# usbxlater.net
KiCad netlist of a schematic drawn in EAGLE
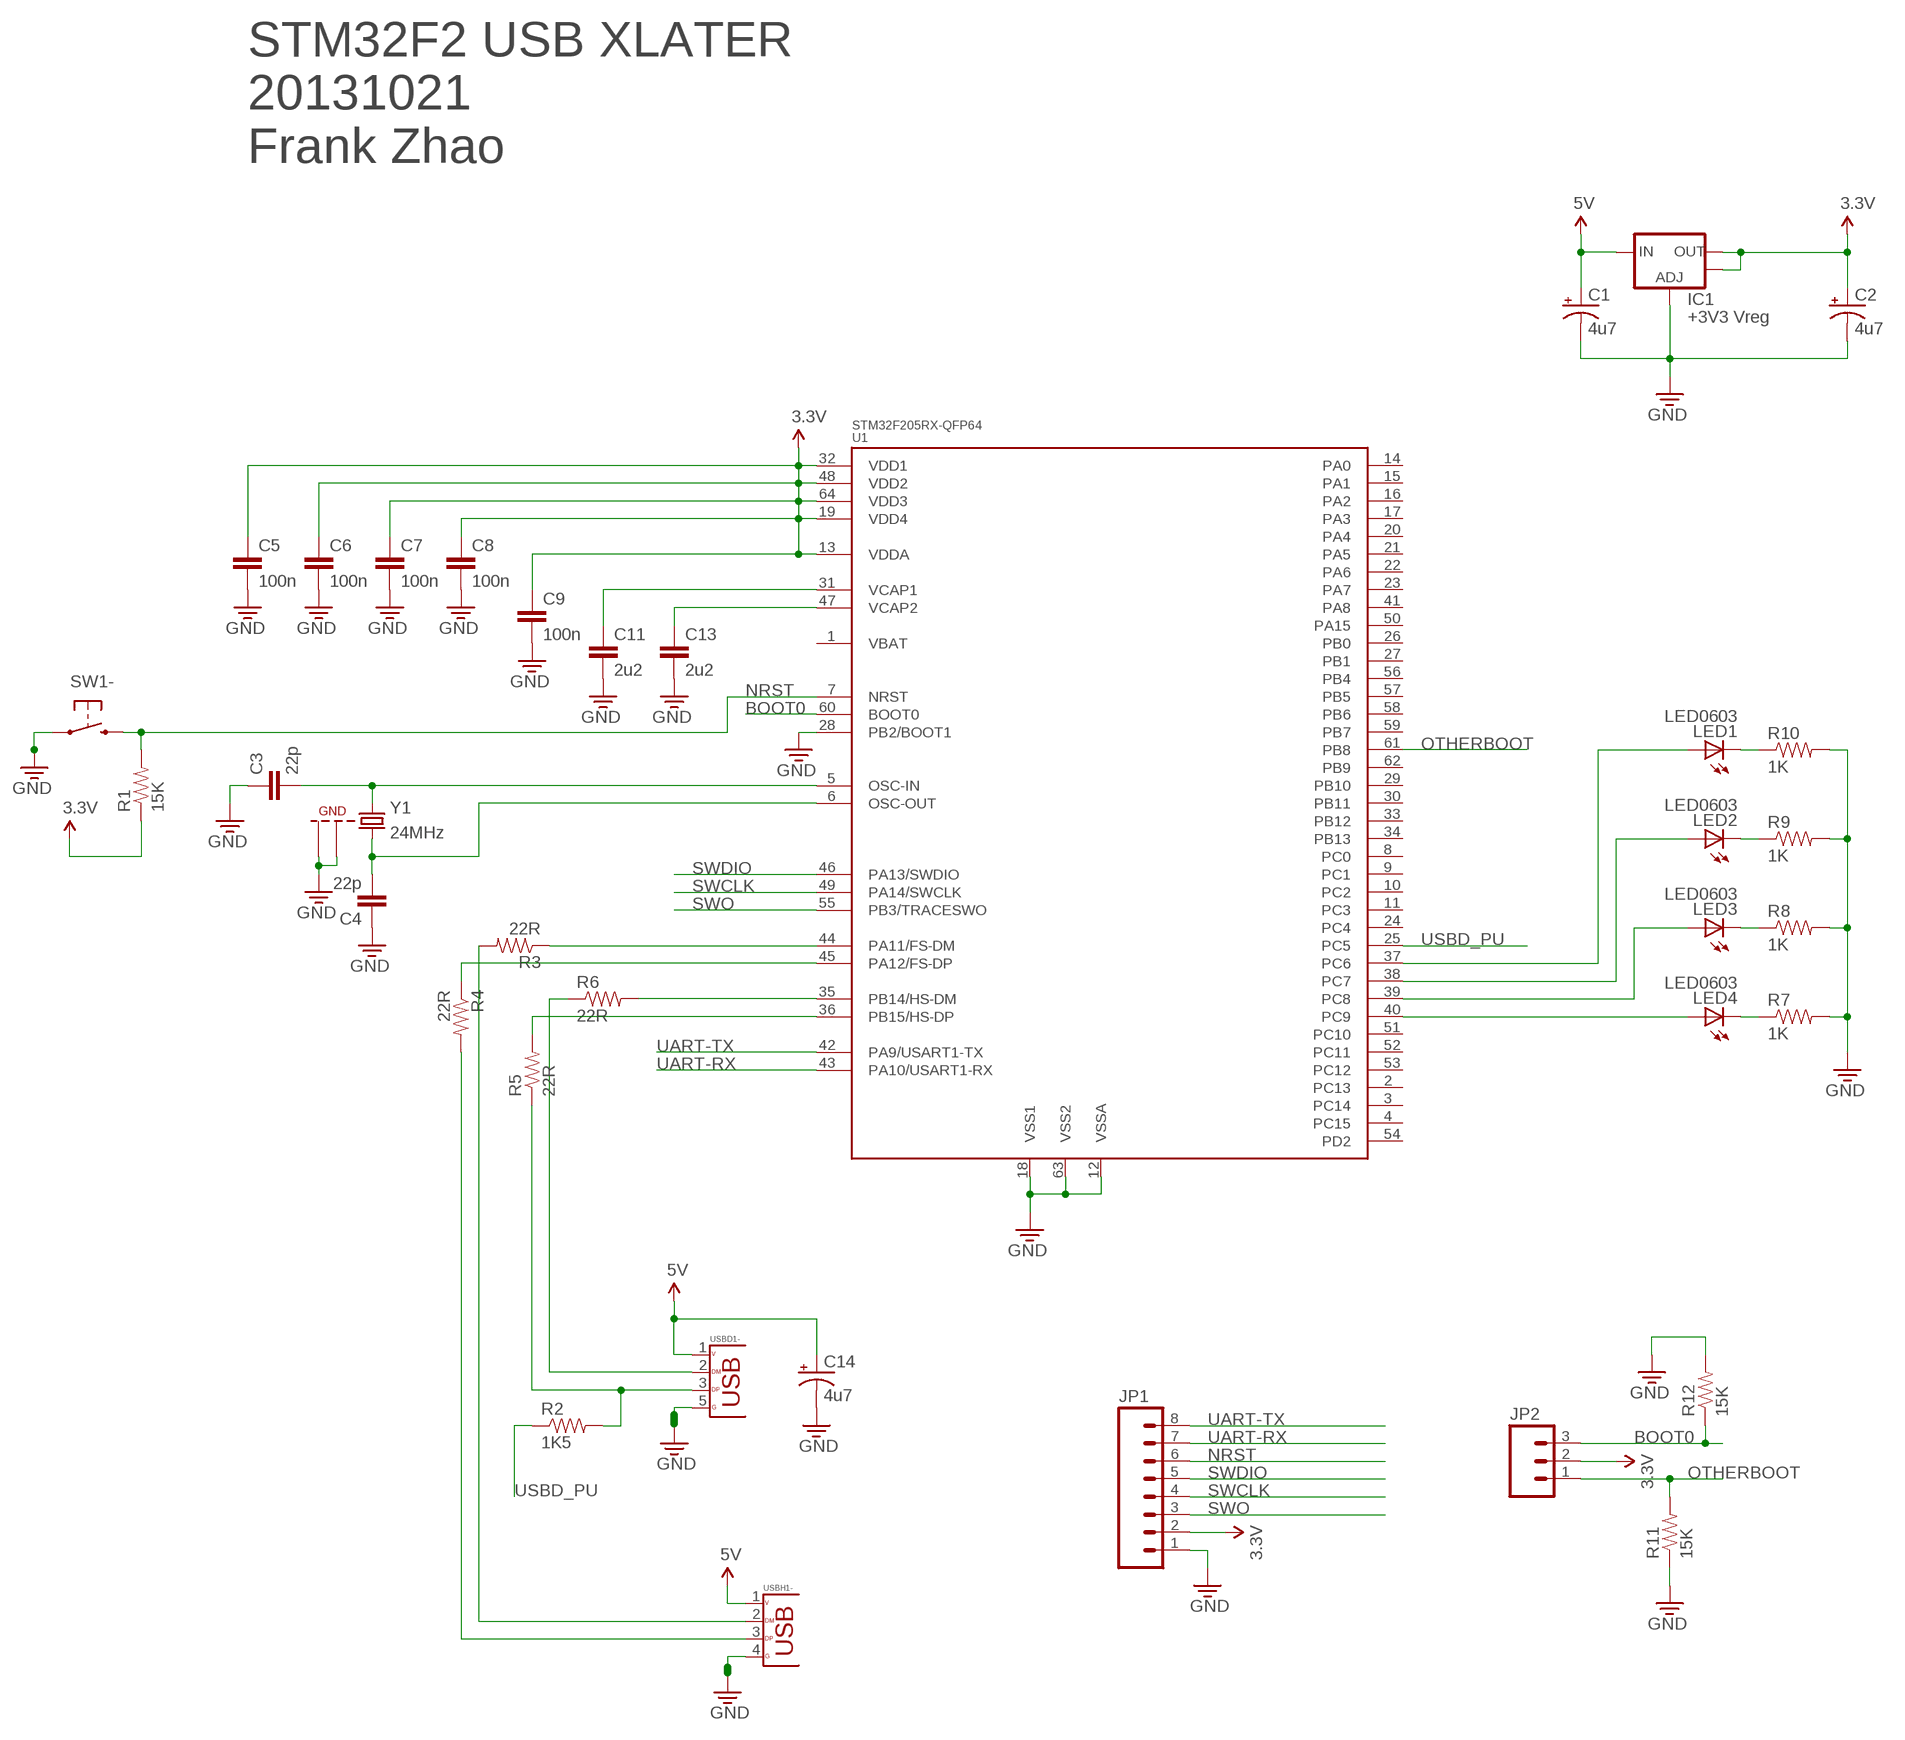
[diagram p0: schematic, sheet 1]

(export (version "E")
  (design (tool "Eeschema 10.0.6"))
  (components
    (comp (ref "C1")
      (value "4u7")
      (footprint "eagle-import:EIA3216")
      (libsource (lib "eagle-import") (part "CAP_POL1206"))
    )
    (comp (ref "C2")
      (value "4u7")
      (footprint "eagle-import:EIA3216")
      (libsource (lib "eagle-import") (part "CAP_POL1206"))
    )
    (comp (ref "C3")
      (value "22p")
      (footprint "eagle-import:0603-CAP-NOLEAK")
      (libsource (lib "eagle-import") (part "CAP0603-CAP-NOLEAK"))
    )
    (comp (ref "C4")
      (value "22p")
      (footprint "eagle-import:0603-CAP-NOLEAK")
      (libsource (lib "eagle-import") (part "CAP0603-CAP-NOLEAK"))
    )
    (comp (ref "C5")
      (value "100n")
      (footprint "eagle-import:0603-CAP-NOLEAK")
      (libsource (lib "eagle-import") (part "CAP0603-CAP-NOLEAK"))
    )
    (comp (ref "C6")
      (value "100n")
      (footprint "eagle-import:0603-CAP-NOLEAK")
      (libsource (lib "eagle-import") (part "CAP0603-CAP-NOLEAK"))
    )
    (comp (ref "C7")
      (value "100n")
      (footprint "eagle-import:0603-CAP-NOLEAK")
      (libsource (lib "eagle-import") (part "CAP0603-CAP-NOLEAK"))
    )
    (comp (ref "C8")
      (value "100n")
      (footprint "eagle-import:0603-CAP-NOLEAK")
      (libsource (lib "eagle-import") (part "CAP0603-CAP-NOLEAK"))
    )
    (comp (ref "C9")
      (value "100n")
      (footprint "eagle-import:0603-CAP-NOLEAK")
      (libsource (lib "eagle-import") (part "CAP0603-CAP-NOLEAK"))
    )
    (comp (ref "C11")
      (value "2u2")
      (footprint "eagle-import:0603-CAP-NOLEAK")
      (libsource (lib "eagle-import") (part "CAP0603-CAP-NOLEAK"))
    )
    (comp (ref "C13")
      (value "2u2")
      (footprint "eagle-import:0603-CAP-NOLEAK")
      (libsource (lib "eagle-import") (part "CAP0603-CAP-NOLEAK"))
    )
    (comp (ref "C14")
      (value "4u7")
      (footprint "eagle-import:EIA3216")
      (libsource (lib "eagle-import") (part "CAP_POL1206"))
    )
    (comp (ref "IC1")
      (value "+3V3 Vreg")
      (footprint "eagle-import:SOT223")
      (libsource (lib "eagle-import") (part "V_REG_LM1117SOT223"))
    )
    (comp (ref "JP1")
      (value "M081X08")
      (footprint "eagle-import:1X08")
      (libsource (lib "eagle-import") (part "M081X08"))
    )
    (comp (ref "JP2")
      (value "M03PTH")
      (footprint "eagle-import:1X03")
      (libsource (lib "eagle-import") (part "M03PTH"))
    )
    (comp (ref "LED1")
      (value "LED0603")
      (footprint "eagle-import:LED-0603")
      (libsource (lib "eagle-import") (part "LED0603"))
    )
    (comp (ref "LED2")
      (value "LED0603")
      (footprint "eagle-import:LED-0603")
      (libsource (lib "eagle-import") (part "LED0603"))
    )
    (comp (ref "LED3")
      (value "LED0603")
      (footprint "eagle-import:LED-0603")
      (libsource (lib "eagle-import") (part "LED0603"))
    )
    (comp (ref "LED4")
      (value "LED0603")
      (footprint "eagle-import:LED-0603")
      (libsource (lib "eagle-import") (part "LED0603"))
    )
    (comp (ref "R1")
      (value "15K")
      (footprint "eagle-import:0603-RES")
      (libsource (lib "eagle-import") (part "RESISTOR0603-RES"))
    )
    (comp (ref "R2")
      (value "1K5")
      (footprint "eagle-import:0603-RES")
      (libsource (lib "eagle-import") (part "RESISTOR0603-RES"))
    )
    (comp (ref "R3")
      (value "22R")
      (footprint "eagle-import:0603-RES")
      (libsource (lib "eagle-import") (part "RESISTOR0603-RES"))
    )
    (comp (ref "R4")
      (value "22R")
      (footprint "eagle-import:0603-RES")
      (libsource (lib "eagle-import") (part "RESISTOR0603-RES"))
    )
    (comp (ref "R5")
      (value "22R")
      (footprint "eagle-import:0603-RES")
      (libsource (lib "eagle-import") (part "RESISTOR0603-RES"))
    )
    (comp (ref "R6")
      (value "22R")
      (footprint "eagle-import:0603-RES")
      (libsource (lib "eagle-import") (part "RESISTOR0603-RES"))
    )
    (comp (ref "R7")
      (value "1K")
      (footprint "eagle-import:0603-RES-NOLEAK")
      (libsource (lib "eagle-import") (part "RESISTOR0603-RES-NOLEAK"))
    )
    (comp (ref "R8")
      (value "1K")
      (footprint "eagle-import:0603-RES")
      (libsource (lib "eagle-import") (part "RESISTOR0603-RES"))
    )
    (comp (ref "R9")
      (value "1K")
      (footprint "eagle-import:0603-RES-NOLEAK")
      (libsource (lib "eagle-import") (part "RESISTOR0603-RES-NOLEAK"))
    )
    (comp (ref "R10")
      (value "1K")
      (footprint "eagle-import:0603-RES")
      (libsource (lib "eagle-import") (part "RESISTOR0603-RES"))
    )
    (comp (ref "R11")
      (value "15K")
      (footprint "eagle-import:0603-RES-NOLEAK")
      (libsource (lib "eagle-import") (part "RESISTOR0603-RES-NOLEAK"))
    )
    (comp (ref "R12")
      (value "15K")
      (footprint "eagle-import:0603-RES-NOLEAK")
      (libsource (lib "eagle-import") (part "RESISTOR0603-RES-NOLEAK"))
    )
    (comp (ref "SW1")
      (value "SWITCH-B3U-1100-BOSS")
      (footprint "eagle-import:SWITCH-TACT-B3U-1100P-B")
      (libsource (lib "eagle-import") (part "SWITCH-B3U-1100-BOSS"))
    )
    (comp (ref "U1")
      (value "STM32F205RX-QFP64")
      (footprint "eagle-import:TQFP64")
      (libsource (lib "eagle-import") (part "STM32F205RX-QFP64"))
    )
    (comp (ref "USBD1")
      (value "USB-6S-MICRO_B")
      (footprint "eagle-import:USB_MICRO_B")
      (libsource (lib "eagle-import") (part "USB-6S-MICRO_B"))
    )
    (comp (ref "USBH1")
      (value "USB-A-RV")
      (footprint "eagle-import:USB-A-RV")
      (libsource (lib "eagle-import") (part "USB-A-RV"))
    )
    (comp (ref "Y1")
      (value "24MHz")
      (footprint "eagle-import:CRYSTAL-SMD-3.2X2.5")
      (libsource (lib "eagle-import") (part "CRYSTAL_SMD_GND-3.2X2.5"))
    )
  )
  (nets
    (net (code "1") (name "/BOOT0") (class "Default")
      (node (ref "JP2") (pin "3") (pinfunction "3_3") (pintype "passive"))
      (node (ref "R12") (pin "1") (pinfunction "1_1") (pintype "passive"))
      (node (ref "U1") (pin "60") (pinfunction "BOOT0_60") (pintype "input"))
    )
    (net (code "2") (name "/NRST") (class "Default")
      (node (ref "JP1") (pin "6") (pinfunction "6_6") (pintype "passive"))
      (node (ref "R1") (pin "2") (pinfunction "2_2") (pintype "passive"))
      (node (ref "SW1") (pin "2") (pinfunction "2_2") (pintype "passive"))
      (node (ref "U1") (pin "7") (pinfunction "NRST_7") (pintype "input"))
    )
    (net (code "3") (name "/OTHERBOOT") (class "Default")
      (node (ref "JP2") (pin "1") (pinfunction "1_1") (pintype "passive"))
      (node (ref "R11") (pin "2") (pinfunction "2_2") (pintype "passive"))
      (node (ref "U1") (pin "61") (pinfunction "PB8_61") (pintype "bidirectional"))
    )
    (net (code "4") (name "/SWCLK") (class "Default")
      (node (ref "JP1") (pin "4") (pinfunction "4_4") (pintype "passive"))
      (node (ref "U1") (pin "49") (pinfunction "PA14/SWCLK_49") (pintype "bidirectional"))
    )
    (net (code "5") (name "/SWDIO") (class "Default")
      (node (ref "JP1") (pin "5") (pinfunction "5_5") (pintype "passive"))
      (node (ref "U1") (pin "46") (pinfunction "PA13/SWDIO_46") (pintype "bidirectional"))
    )
    (net (code "6") (name "/SWO") (class "Default")
      (node (ref "JP1") (pin "3") (pinfunction "3_3") (pintype "passive"))
      (node (ref "U1") (pin "55") (pinfunction "PB3/TRACESWO_55") (pintype "bidirectional"))
    )
    (net (code "7") (name "/UART-RX") (class "Default")
      (node (ref "JP1") (pin "7") (pinfunction "7_7") (pintype "passive"))
      (node (ref "U1") (pin "43") (pinfunction "PA10/USART1-RX_43") (pintype "bidirectional"))
    )
    (net (code "8") (name "/UART-TX") (class "Default")
      (node (ref "JP1") (pin "8") (pinfunction "8_8") (pintype "passive"))
      (node (ref "U1") (pin "42") (pinfunction "PA9/USART1-TX_42") (pintype "bidirectional"))
    )
    (net (code "9") (name "/USBD_PU") (class "Default")
      (node (ref "R2") (pin "1") (pinfunction "1_1") (pintype "passive"))
      (node (ref "U1") (pin "25") (pinfunction "PC5_25") (pintype "bidirectional"))
    )
    (net (code "10") (name "3.3V") (class "Default")
      (node (ref "C2") (pin "A") (pinfunction "+_A") (pintype "passive"))
      (node (ref "C5") (pin "1") (pinfunction "1_1") (pintype "passive"))
      (node (ref "C6") (pin "1") (pinfunction "1_1") (pintype "passive"))
      (node (ref "C7") (pin "1") (pinfunction "1_1") (pintype "passive"))
      (node (ref "C8") (pin "1") (pinfunction "1_1") (pintype "passive"))
      (node (ref "C9") (pin "1") (pinfunction "1_1") (pintype "passive"))
      (node (ref "IC1") (pin "2") (pinfunction "OUT_2") (pintype "output"))
      (node (ref "IC1") (pin "4") (pinfunction "OUT_4") (pintype "output"))
      (node (ref "JP1") (pin "2") (pinfunction "2_2") (pintype "passive"))
      (node (ref "JP2") (pin "2") (pinfunction "2_2") (pintype "passive"))
      (node (ref "R1") (pin "1") (pinfunction "1_1") (pintype "passive"))
      (node (ref "U1") (pin "13") (pinfunction "VDDA_13") (pintype "bidirectional"))
      (node (ref "U1") (pin "19") (pinfunction "VDD4_19") (pintype "bidirectional"))
      (node (ref "U1") (pin "32") (pinfunction "VDD1_32") (pintype "bidirectional"))
      (node (ref "U1") (pin "48") (pinfunction "VDD2_48") (pintype "bidirectional"))
      (node (ref "U1") (pin "64") (pinfunction "VDD3_64") (pintype "bidirectional"))
    )
    (net (code "11") (name "5V") (class "Default")
      (node (ref "C1") (pin "A") (pinfunction "+_A") (pintype "passive"))
      (node (ref "C14") (pin "A") (pinfunction "+_A") (pintype "passive"))
      (node (ref "IC1") (pin "3") (pinfunction "IN_3") (pintype "input"))
      (node (ref "USBD1") (pin "1") (pinfunction "VBUS_1") (pintype "bidirectional"))
      (node (ref "USBH1") (pin "1") (pinfunction "VBUS_1") (pintype "bidirectional"))
    )
    (net (code "12") (name "GND") (class "Default")
      (node (ref "C1") (pin "C") (pinfunction "-_C") (pintype "passive"))
      (node (ref "C11") (pin "2") (pinfunction "2_2") (pintype "passive"))
      (node (ref "C13") (pin "2") (pinfunction "2_2") (pintype "passive"))
      (node (ref "C14") (pin "C") (pinfunction "-_C") (pintype "passive"))
      (node (ref "C2") (pin "C") (pinfunction "-_C") (pintype "passive"))
      (node (ref "C3") (pin "1") (pinfunction "1_1") (pintype "passive"))
      (node (ref "C4") (pin "1") (pinfunction "1_1") (pintype "passive"))
      (node (ref "C5") (pin "2") (pinfunction "2_2") (pintype "passive"))
      (node (ref "C6") (pin "2") (pinfunction "2_2") (pintype "passive"))
      (node (ref "C7") (pin "2") (pinfunction "2_2") (pintype "passive"))
      (node (ref "C8") (pin "2") (pinfunction "2_2") (pintype "passive"))
      (node (ref "C9") (pin "2") (pinfunction "2_2") (pintype "passive"))
      (node (ref "IC1") (pin "1") (pinfunction "ADJ_1") (pintype "input"))
      (node (ref "JP1") (pin "1") (pinfunction "1_1") (pintype "passive"))
      (node (ref "R10") (pin "2") (pinfunction "2_2") (pintype "passive"))
      (node (ref "R11") (pin "1") (pinfunction "1_1") (pintype "passive"))
      (node (ref "R12") (pin "2") (pinfunction "2_2") (pintype "passive"))
      (node (ref "R7") (pin "2") (pinfunction "2_2") (pintype "passive"))
      (node (ref "R8") (pin "2") (pinfunction "2_2") (pintype "passive"))
      (node (ref "R9") (pin "2") (pinfunction "2_2") (pintype "passive"))
      (node (ref "SW1") (pin "1") (pinfunction "1_1") (pintype "passive"))
      (node (ref "SW1") (pin "BOSS") (pinfunction "P$1_BOSS") (pintype "bidirectional"))
      (node (ref "U1") (pin "12") (pinfunction "VSSA_12") (pintype "bidirectional"))
      (node (ref "U1") (pin "18") (pinfunction "VSS1_18") (pintype "bidirectional"))
      (node (ref "U1") (pin "28") (pinfunction "PB2/BOOT1_28") (pintype "bidirectional"))
      (node (ref "U1") (pin "63") (pinfunction "VSS2_63") (pintype "bidirectional"))
      (node (ref "USBD1") (pin "5") (pinfunction "GND_5") (pintype "bidirectional"))
      (node (ref "USBD1") (pin "P$1") (pinfunction "P$1_P$1") (pintype "bidirectional"))
      (node (ref "USBD1") (pin "P$2") (pinfunction "P$1_P$2") (pintype "bidirectional"))
      (node (ref "USBD1") (pin "P$3") (pinfunction "P$1_P$3") (pintype "bidirectional"))
      (node (ref "USBD1") (pin "P$4") (pinfunction "P$1_P$4") (pintype "bidirectional"))
      (node (ref "USBD1") (pin "S1") (pinfunction "P$1_S1") (pintype "bidirectional"))
      (node (ref "USBD1") (pin "S2") (pinfunction "P$1_S2") (pintype "bidirectional"))
      (node (ref "USBH1") (pin "4") (pinfunction "GND_4") (pintype "bidirectional"))
      (node (ref "USBH1") (pin "S1") (pinfunction "P$1_S1") (pintype "bidirectional"))
      (node (ref "USBH1") (pin "S2") (pinfunction "P$1_S2") (pintype "bidirectional"))
      (node (ref "USBH1") (pin "S3") (pinfunction "P$1_S3") (pintype "bidirectional"))
      (node (ref "USBH1") (pin "S4") (pinfunction "P$1_S4") (pintype "bidirectional"))
      (node (ref "Y1") (pin "2") (pinfunction "GND1_2") (pintype "bidirectional"))
      (node (ref "Y1") (pin "4") (pinfunction "GND2_4") (pintype "bidirectional"))
    )
    (net (code "13") (name "Net-(LED1-PadC)") (class "Default")
      (node (ref "LED1") (pin "C") (pinfunction "C_C") (pintype "passive"))
      (node (ref "R10") (pin "1") (pinfunction "1_1") (pintype "passive"))
    )
    (net (code "14") (name "Net-(LED2-PadC)") (class "Default")
      (node (ref "LED2") (pin "C") (pinfunction "C_C") (pintype "passive"))
      (node (ref "R9") (pin "1") (pinfunction "1_1") (pintype "passive"))
    )
    (net (code "15") (name "Net-(LED3-PadC)") (class "Default")
      (node (ref "LED3") (pin "C") (pinfunction "C_C") (pintype "passive"))
      (node (ref "R8") (pin "1") (pinfunction "1_1") (pintype "passive"))
    )
    (net (code "16") (name "Net-(LED4-PadC)") (class "Default")
      (node (ref "LED4") (pin "C") (pinfunction "C_C") (pintype "passive"))
      (node (ref "R7") (pin "1") (pinfunction "1_1") (pintype "passive"))
    )
    (net (code "17") (name "Net-(U1-OSC-IN)") (class "Default")
      (node (ref "C3") (pin "2") (pinfunction "2_2") (pintype "passive"))
      (node (ref "U1") (pin "5") (pinfunction "OSC-IN_5") (pintype "bidirectional"))
      (node (ref "Y1") (pin "1") (pinfunction "1_1") (pintype "passive"))
    )
    (net (code "18") (name "Net-(U1-OSC-OUT)") (class "Default")
      (node (ref "C4") (pin "2") (pinfunction "2_2") (pintype "passive"))
      (node (ref "U1") (pin "6") (pinfunction "OSC-OUT_6") (pintype "bidirectional"))
      (node (ref "Y1") (pin "3") (pinfunction "2_3") (pintype "passive"))
    )
    (net (code "19") (name "Net-(U1-PA11{slash}FS-DM)") (class "Default")
      (node (ref "R3") (pin "1") (pinfunction "1_1") (pintype "passive"))
      (node (ref "U1") (pin "44") (pinfunction "PA11/FS-DM_44") (pintype "bidirectional"))
    )
    (net (code "20") (name "Net-(U1-PA12{slash}FS-DP)") (class "Default")
      (node (ref "R4") (pin "1") (pinfunction "1_1") (pintype "passive"))
      (node (ref "U1") (pin "45") (pinfunction "PA12/FS-DP_45") (pintype "bidirectional"))
    )
    (net (code "21") (name "Net-(U1-PB14{slash}HS-DM)") (class "Default")
      (node (ref "R6") (pin "2") (pinfunction "2_2") (pintype "passive"))
      (node (ref "U1") (pin "35") (pinfunction "PB14/HS-DM_35") (pintype "bidirectional"))
    )
    (net (code "22") (name "Net-(U1-PB15{slash}HS-DP)") (class "Default")
      (node (ref "R5") (pin "2") (pinfunction "2_2") (pintype "passive"))
      (node (ref "U1") (pin "36") (pinfunction "PB15/HS-DP_36") (pintype "bidirectional"))
    )
    (net (code "23") (name "Net-(U1-PC6)") (class "Default")
      (node (ref "LED1") (pin "A") (pinfunction "A_A") (pintype "passive"))
      (node (ref "U1") (pin "37") (pinfunction "PC6_37") (pintype "bidirectional"))
    )
    (net (code "24") (name "Net-(U1-PC7)") (class "Default")
      (node (ref "LED2") (pin "A") (pinfunction "A_A") (pintype "passive"))
      (node (ref "U1") (pin "38") (pinfunction "PC7_38") (pintype "bidirectional"))
    )
    (net (code "25") (name "Net-(U1-PC8)") (class "Default")
      (node (ref "LED3") (pin "A") (pinfunction "A_A") (pintype "passive"))
      (node (ref "U1") (pin "39") (pinfunction "PC8_39") (pintype "bidirectional"))
    )
    (net (code "26") (name "Net-(U1-PC9)") (class "Default")
      (node (ref "LED4") (pin "A") (pinfunction "A_A") (pintype "passive"))
      (node (ref "U1") (pin "40") (pinfunction "PC9_40") (pintype "bidirectional"))
    )
    (net (code "27") (name "Net-(U1-VCAP1)") (class "Default")
      (node (ref "C11") (pin "1") (pinfunction "1_1") (pintype "passive"))
      (node (ref "U1") (pin "31") (pinfunction "VCAP1_31") (pintype "bidirectional"))
    )
    (net (code "28") (name "Net-(U1-VCAP2)") (class "Default")
      (node (ref "C13") (pin "1") (pinfunction "1_1") (pintype "passive"))
      (node (ref "U1") (pin "47") (pinfunction "VCAP2_47") (pintype "bidirectional"))
    )
    (net (code "29") (name "Net-(USBD1A-D+)") (class "Default")
      (node (ref "R2") (pin "2") (pinfunction "2_2") (pintype "passive"))
      (node (ref "R5") (pin "1") (pinfunction "1_1") (pintype "passive"))
      (node (ref "USBD1") (pin "3") (pinfunction "D+_3") (pintype "bidirectional"))
    )
    (net (code "30") (name "Net-(USBD1A-D-)") (class "Default")
      (node (ref "R6") (pin "1") (pinfunction "1_1") (pintype "passive"))
      (node (ref "USBD1") (pin "2") (pinfunction "D-_2") (pintype "bidirectional"))
    )
    (net (code "31") (name "Net-(USBH1A-D+)") (class "Default")
      (node (ref "R4") (pin "2") (pinfunction "2_2") (pintype "passive"))
      (node (ref "USBH1") (pin "3") (pinfunction "D+_3") (pintype "bidirectional"))
    )
    (net (code "32") (name "Net-(USBH1A-D-)") (class "Default")
      (node (ref "R3") (pin "2") (pinfunction "2_2") (pintype "passive"))
      (node (ref "USBH1") (pin "2") (pinfunction "D-_2") (pintype "bidirectional"))
    )
    (net (code "33") (name "unconnected-(U1-PA0-Pad14)") (class "Default")
      (node (ref "U1") (pin "14") (pinfunction "PA0_14") (pintype "bidirectional"))
    )
    (net (code "34") (name "unconnected-(U1-PA1-Pad15)") (class "Default")
      (node (ref "U1") (pin "15") (pinfunction "PA1_15") (pintype "bidirectional"))
    )
    (net (code "35") (name "unconnected-(U1-PA2-Pad16)") (class "Default")
      (node (ref "U1") (pin "16") (pinfunction "PA2_16") (pintype "bidirectional"))
    )
    (net (code "36") (name "unconnected-(U1-PA3-Pad17)") (class "Default")
      (node (ref "U1") (pin "17") (pinfunction "PA3_17") (pintype "bidirectional"))
    )
    (net (code "37") (name "unconnected-(U1-PA4-Pad20)") (class "Default")
      (node (ref "U1") (pin "20") (pinfunction "PA4_20") (pintype "bidirectional"))
    )
    (net (code "38") (name "unconnected-(U1-PA5-Pad21)") (class "Default")
      (node (ref "U1") (pin "21") (pinfunction "PA5_21") (pintype "bidirectional"))
    )
    (net (code "39") (name "unconnected-(U1-PA6-Pad22)") (class "Default")
      (node (ref "U1") (pin "22") (pinfunction "PA6_22") (pintype "bidirectional"))
    )
    (net (code "40") (name "unconnected-(U1-PA7-Pad23)") (class "Default")
      (node (ref "U1") (pin "23") (pinfunction "PA7_23") (pintype "bidirectional"))
    )
    (net (code "41") (name "unconnected-(U1-PA8-Pad41)") (class "Default")
      (node (ref "U1") (pin "41") (pinfunction "PA8_41") (pintype "bidirectional"))
    )
    (net (code "42") (name "unconnected-(U1-PA15-Pad50)") (class "Default")
      (node (ref "U1") (pin "50") (pinfunction "PA15_50") (pintype "bidirectional"))
    )
    (net (code "43") (name "unconnected-(U1-PB0-Pad26)") (class "Default")
      (node (ref "U1") (pin "26") (pinfunction "PB0_26") (pintype "bidirectional"))
    )
    (net (code "44") (name "unconnected-(U1-PB1-Pad27)") (class "Default")
      (node (ref "U1") (pin "27") (pinfunction "PB1_27") (pintype "bidirectional"))
    )
    (net (code "45") (name "unconnected-(U1-PB4-Pad56)") (class "Default")
      (node (ref "U1") (pin "56") (pinfunction "PB4_56") (pintype "bidirectional"))
    )
    (net (code "46") (name "unconnected-(U1-PB5-Pad57)") (class "Default")
      (node (ref "U1") (pin "57") (pinfunction "PB5_57") (pintype "bidirectional"))
    )
    (net (code "47") (name "unconnected-(U1-PB6-Pad58)") (class "Default")
      (node (ref "U1") (pin "58") (pinfunction "PB6_58") (pintype "bidirectional"))
    )
    (net (code "48") (name "unconnected-(U1-PB7-Pad59)") (class "Default")
      (node (ref "U1") (pin "59") (pinfunction "PB7_59") (pintype "bidirectional"))
    )
    (net (code "49") (name "unconnected-(U1-PB9-Pad62)") (class "Default")
      (node (ref "U1") (pin "62") (pinfunction "PB9_62") (pintype "bidirectional"))
    )
    (net (code "50") (name "unconnected-(U1-PB10-Pad29)") (class "Default")
      (node (ref "U1") (pin "29") (pinfunction "PB10_29") (pintype "bidirectional"))
    )
    (net (code "51") (name "unconnected-(U1-PB11-Pad30)") (class "Default")
      (node (ref "U1") (pin "30") (pinfunction "PB11_30") (pintype "bidirectional"))
    )
    (net (code "52") (name "unconnected-(U1-PB12-Pad33)") (class "Default")
      (node (ref "U1") (pin "33") (pinfunction "PB12_33") (pintype "bidirectional"))
    )
    (net (code "53") (name "unconnected-(U1-PB13-Pad34)") (class "Default")
      (node (ref "U1") (pin "34") (pinfunction "PB13_34") (pintype "bidirectional"))
    )
    (net (code "54") (name "unconnected-(U1-PC0-Pad8)") (class "Default")
      (node (ref "U1") (pin "8") (pinfunction "PC0_8") (pintype "bidirectional"))
    )
    (net (code "55") (name "unconnected-(U1-PC1-Pad9)") (class "Default")
      (node (ref "U1") (pin "9") (pinfunction "PC1_9") (pintype "bidirectional"))
    )
    (net (code "56") (name "unconnected-(U1-PC2-Pad10)") (class "Default")
      (node (ref "U1") (pin "10") (pinfunction "PC2_10") (pintype "bidirectional"))
    )
    (net (code "57") (name "unconnected-(U1-PC3-Pad11)") (class "Default")
      (node (ref "U1") (pin "11") (pinfunction "PC3_11") (pintype "bidirectional"))
    )
    (net (code "58") (name "unconnected-(U1-PC4-Pad24)") (class "Default")
      (node (ref "U1") (pin "24") (pinfunction "PC4_24") (pintype "bidirectional"))
    )
    (net (code "59") (name "unconnected-(U1-PC10-Pad51)") (class "Default")
      (node (ref "U1") (pin "51") (pinfunction "PC10_51") (pintype "bidirectional"))
    )
    (net (code "60") (name "unconnected-(U1-PC11-Pad52)") (class "Default")
      (node (ref "U1") (pin "52") (pinfunction "PC11_52") (pintype "bidirectional"))
    )
    (net (code "61") (name "unconnected-(U1-PC12-Pad53)") (class "Default")
      (node (ref "U1") (pin "53") (pinfunction "PC12_53") (pintype "bidirectional"))
    )
    (net (code "62") (name "unconnected-(U1-PC13-Pad2)") (class "Default")
      (node (ref "U1") (pin "2") (pinfunction "PC13_2") (pintype "bidirectional"))
    )
    (net (code "63") (name "unconnected-(U1-PC14-Pad3)") (class "Default")
      (node (ref "U1") (pin "3") (pinfunction "PC14_3") (pintype "bidirectional"))
    )
    (net (code "64") (name "unconnected-(U1-PC15-Pad4)") (class "Default")
      (node (ref "U1") (pin "4") (pinfunction "PC15_4") (pintype "bidirectional"))
    )
    (net (code "65") (name "unconnected-(U1-PD2-Pad54)") (class "Default")
      (node (ref "U1") (pin "54") (pinfunction "PD2_54") (pintype "bidirectional"))
    )
    (net (code "66") (name "unconnected-(U1-VBAT-Pad1)") (class "Default")
      (node (ref "U1") (pin "1") (pinfunction "VBAT_1") (pintype "input"))
    )
  )
)
